# RS485.net
KiCad netlist of a schematic drawn in Altium Designer
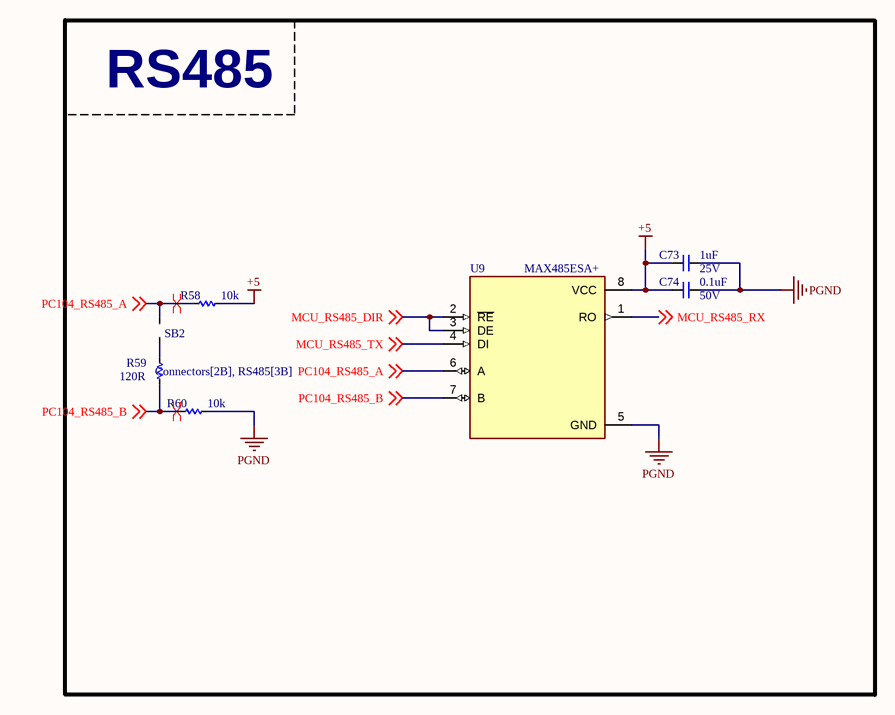
[diagram p0: RS485.SchDoc]

(export (version "E")
  (design (tool "Eeschema 10.0.6"))
  (components
    (comp (ref "C73")
      (value "1uF")
      (footprint "CAP_C_1608X80")
      (description "CAP")
      (fields (field (name "VOLTAGE") "25V"))
      (libsource (lib "LABLIB") (part "_CAP_C_2"))
    )
    (comp (ref "C74")
      (value "0.1uF")
      (footprint "CAP_C_1608X80")
      (description "CAP")
      (fields (field (name "VOLTAGE") "50V"))
      (libsource (lib "LABLIB") (part "_CAP_C_2"))
    )
    (comp (ref "R58")
      (value "10k")
      (footprint "RES_C_1608X60")
      (description "RES")
      (libsource (lib "LABLIB") (part "_RES_B_2_2"))
    )
    (comp (ref "R59")
      (value "120R")
      (footprint "RES_C_1608X60")
      (description "RES")
      (libsource (lib "LABLIB") (part "_RES_B_2_2"))
    )
    (comp (ref "R60")
      (value "10k")
      (footprint "RES_C_1608X60")
      (description "RES")
      (libsource (lib "LABLIB") (part "_RES_B_2_2"))
    )
    (comp (ref "SB2") (value "N/A") (footprint "JUMPER_1608") (libsource (lib "LV") (part "JUMPER")))
    (comp (ref "U9")
      (value "MAX485ESA+")
      (footprint "SOIC127")
      (libsource (lib "KIENASIY123_LIB") (part "MAX485ESA+"))
    )
  )
  (nets
    (net (code "1") (name "+5") (class "Default")
      (node (ref "C73") (pin "2") (pinfunction "2_2") (pintype "passive"))
      (node (ref "C74") (pin "2") (pinfunction "2_2") (pintype "passive"))
      (node (ref "R58") (pin "2") (pinfunction "2_2") (pintype "passive"))
      (node (ref "U9") (pin "8") (pinfunction "VCC_8") (pintype "power_in"))
    )
    (net (code "2") (name "MCU_RS485_DIR") (class "Default")
      (node (ref "U9") (pin "2") (pinfunction "~{RE}_2") (pintype "input"))
      (node (ref "U9") (pin "3") (pinfunction "DE_3") (pintype "input"))
    )
    (net (code "3") (name "MCU_RS485_RX") (class "Default")
      (node (ref "U9") (pin "1") (pinfunction "RO_1") (pintype "output"))
    )
    (net (code "4") (name "MCU_RS485_TX") (class "Default")
      (node (ref "U9") (pin "4") (pinfunction "DI_4") (pintype "input"))
    )
    (net (code "5") (name "Net-(R59-Pad2)") (class "Default")
      (node (ref "R59") (pin "2") (pinfunction "2_2") (pintype "passive"))
      (node (ref "SB2") (pin "1") (pinfunction "1_1") (pintype "passive"))
    )
    (net (code "6") (name "PC104_RS485_A") (class "Default")
      (node (ref "R58") (pin "1") (pinfunction "1_1") (pintype "passive"))
      (node (ref "SB2") (pin "2") (pinfunction "2_2") (pintype "passive"))
      (node (ref "U9") (pin "6") (pinfunction "A_6") (pintype "bidirectional"))
    )
    (net (code "7") (name "PC104_RS485_B") (class "Default")
      (node (ref "R59") (pin "1") (pinfunction "1_1") (pintype "passive"))
      (node (ref "R60") (pin "1") (pinfunction "1_1") (pintype "passive"))
      (node (ref "U9") (pin "7") (pinfunction "B_7") (pintype "bidirectional"))
    )
    (net (code "8") (name "PGND") (class "Default")
      (node (ref "C73") (pin "1") (pinfunction "1_1") (pintype "passive"))
      (node (ref "C74") (pin "1") (pinfunction "1_1") (pintype "passive"))
      (node (ref "R60") (pin "2") (pinfunction "2_2") (pintype "passive"))
      (node (ref "U9") (pin "5") (pinfunction "GND_5") (pintype "power_in"))
    )
  )
)
